# schematic.net
KiCad netlist of a schematic drawn in Altium Designer
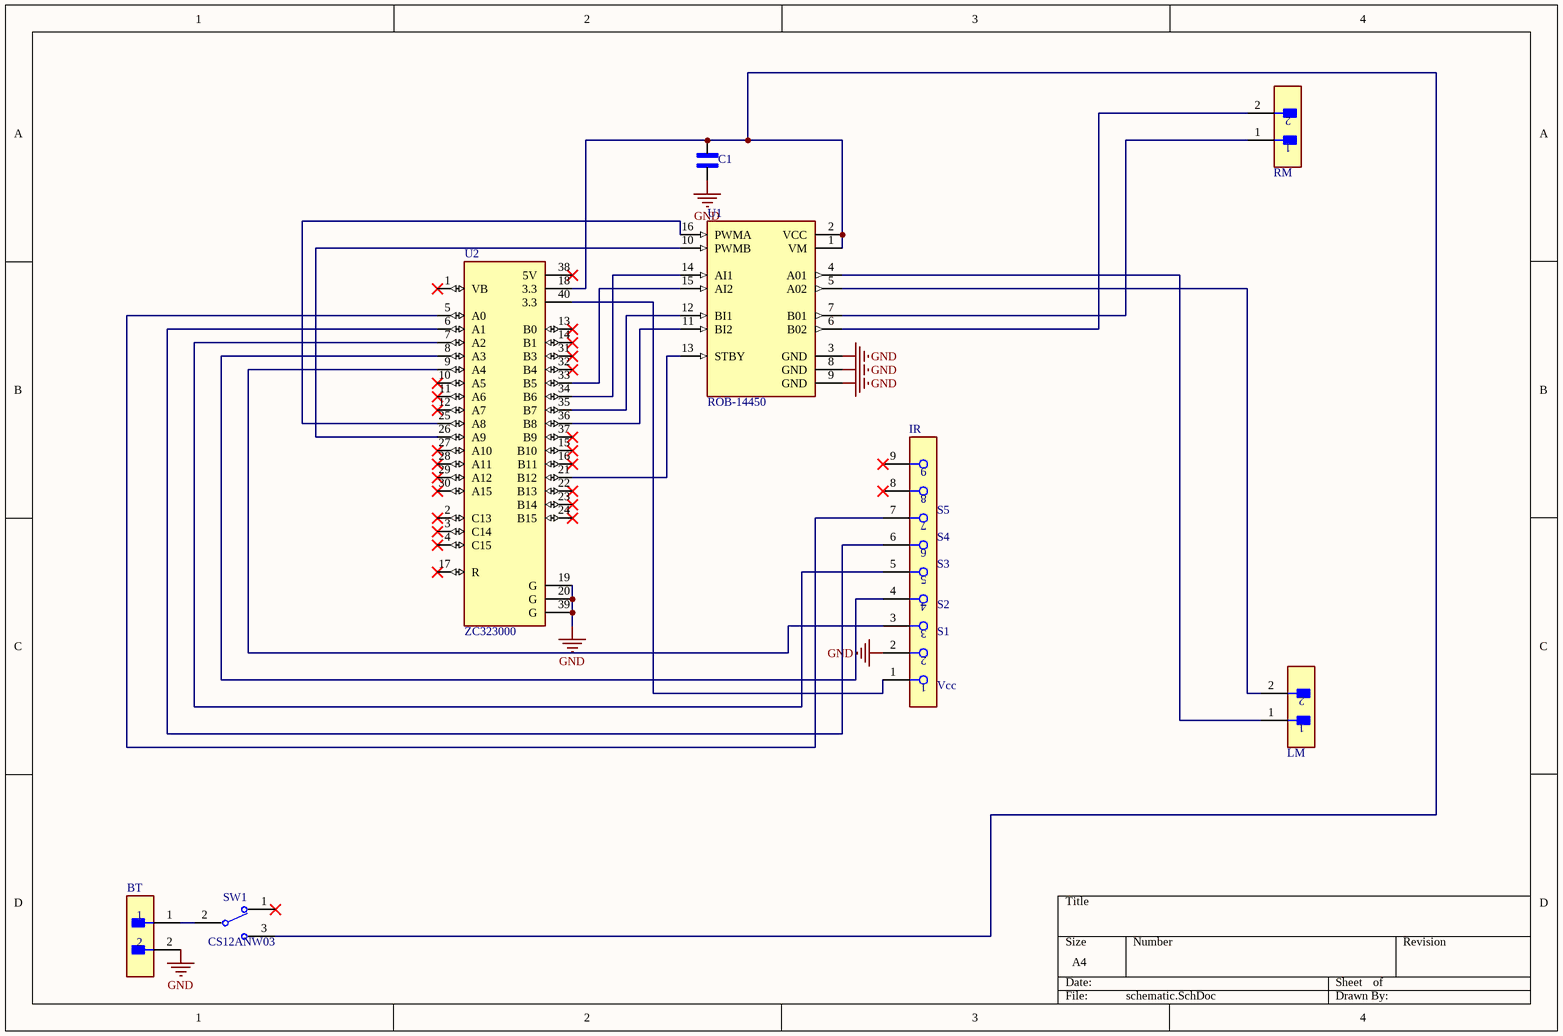
[diagram p0: schematic.SchDoc]

(export (version "E")
  (design (tool "Eeschema 10.0.6"))
  (components
    (comp (ref "BT")
      (value "B2B-XH-AM(LF)(SN)")
      (footprint "FP-B2B-XH-AM_LF_SN-MFG")
      (description "CONN HEADER VERT 2POS 2.5MM")
      (libsource (lib "") (part "3bc925449376181038e59eaffc5286c_1"))
    )
    (comp (ref "C1")
      (value "FA14X8R1H104KNU06")
      (footprint "CAPRB250W50L450T300H550")
      (description "0.1 ÂµF Â±10% 50V Ceramic Capacitor X8R Radial")
      (fields (field (name "MF") "TDK"))
      (libsource (lib "Capacitor_0.1uf") (part "FA14X8R1H104KNU06"))
    )
    (comp (ref "IR")
      (value "CES-109-01-G-S")
      (footprint "FP-CES-109-01-G-S-MFG")
      (description "CES-109-01-G-S Conn Socket Strip SKT 9 POS 2.54mm Solder ST Top Entry Thru-Hole Tube")
      (libsource (lib "Altium Content Vault") (part "d3bf64047269a9dc9b641cdda8ee9d2"))
    )
    (comp (ref "LM")
      (value "TSW-102-12-T-S")
      (footprint "FP-TSW-102-12-T-S-MFG")
      (description "CONN HEADER VERT 2POS 2.54MM")
      (libsource (lib "Altium Content Vault") (part "3bc925449376181038e59eaffc5286c"))
    )
    (comp (ref "RM")
      (value "TSW-102-12-T-S")
      (footprint "FP-TSW-102-12-T-S-MFG")
      (description "CONN HEADER VERT 2POS 2.54MM")
      (libsource (lib "Altium Content Vault") (part "3bc925449376181038e59eaffc5286c"))
    )
    (comp (ref "SW1")
      (value "CS12ANW03")
      (footprint "FP-CS12ANW03-MFG")
      (description "SWITCH SLIDE SPDT 3A 125V")
      (libsource (lib "Altium Content Vault") (part "12161840acc88c497b895bf2e19a5b1"))
    )
    (comp (ref "U1")
      (value "ROB-14450")
      (footprint "MODULE_ROB-14450")
      (description "TB6612FNG Motor Controller/Driver Power Management Evaluation Board")
      (fields (field (name "MF") "SparkFun Electronics"))
      (libsource (lib "DRIVER") (part "ROB-14450"))
    )
    (comp (ref "U2")
      (value "ZC323000")
      (footprint "MODULE_ZC323000")
      (description "STM32F103C8T6 ARM STM32 Minimum System Development Board Module For Arduino")
      (libsource (lib "STM32") (part "ZC323000"))
    )
  )
  (nets
    (net (code "1") (name "GND") (class "Default")
      (node (ref "BT") (pin "2") (pinfunction "2_2") (pintype "passive"))
      (node (ref "C1") (pin "1") (pinfunction "1_1") (pintype "passive"))
      (node (ref "IR") (pin "2") (pinfunction "2_2") (pintype "passive"))
      (node (ref "U1") (pin "3") (pinfunction "GND_3") (pintype "power_in"))
      (node (ref "U1") (pin "8") (pinfunction "GND_8") (pintype "power_in"))
      (node (ref "U1") (pin "9") (pinfunction "GND_9") (pintype "power_in"))
      (node (ref "U2") (pin "19") (pinfunction "G_19") (pintype "power_in"))
      (node (ref "U2") (pin "20") (pinfunction "G_20") (pintype "power_in"))
      (node (ref "U2") (pin "39") (pinfunction "G_39") (pintype "power_in"))
    )
    (net (code "2") (name "Net-(IR-Pad1)") (class "Default")
      (node (ref "IR") (pin "1") (pinfunction "1_1") (pintype "passive"))
      (node (ref "U2") (pin "40") (pinfunction "3.3_40") (pintype "power_in"))
    )
    (net (code "3") (name "Net-(SW1-2(COM))") (class "Default")
      (node (ref "BT") (pin "1") (pinfunction "1_1") (pintype "passive"))
      (node (ref "SW1") (pin "2") (pinfunction "2(COM)_2") (pintype "passive"))
    )
    (net (code "4") (name "Net-(U1-A01)") (class "Default")
      (node (ref "LM") (pin "1") (pinfunction "1_1") (pintype "passive"))
      (node (ref "U1") (pin "4") (pinfunction "A01_4") (pintype "output"))
    )
    (net (code "5") (name "Net-(U1-A02)") (class "Default")
      (node (ref "LM") (pin "2") (pinfunction "2_2") (pintype "passive"))
      (node (ref "U1") (pin "5") (pinfunction "A02_5") (pintype "output"))
    )
    (net (code "6") (name "Net-(U1-AI1)") (class "Default")
      (node (ref "U1") (pin "14") (pinfunction "AI1_14") (pintype "input"))
      (node (ref "U2") (pin "34") (pinfunction "B6_34") (pintype "bidirectional"))
    )
    (net (code "7") (name "Net-(U1-AI2)") (class "Default")
      (node (ref "U1") (pin "15") (pinfunction "AI2_15") (pintype "input"))
      (node (ref "U2") (pin "33") (pinfunction "B5_33") (pintype "bidirectional"))
    )
    (net (code "8") (name "Net-(U1-B01)") (class "Default")
      (node (ref "RM") (pin "1") (pinfunction "1_1") (pintype "passive"))
      (node (ref "U1") (pin "7") (pinfunction "B01_7") (pintype "output"))
    )
    (net (code "9") (name "Net-(U1-B02)") (class "Default")
      (node (ref "RM") (pin "2") (pinfunction "2_2") (pintype "passive"))
      (node (ref "U1") (pin "6") (pinfunction "B02_6") (pintype "output"))
    )
    (net (code "10") (name "Net-(U1-BI1)") (class "Default")
      (node (ref "U1") (pin "12") (pinfunction "BI1_12") (pintype "input"))
      (node (ref "U2") (pin "35") (pinfunction "B7_35") (pintype "bidirectional"))
    )
    (net (code "11") (name "Net-(U1-BI2)") (class "Default")
      (node (ref "U1") (pin "11") (pinfunction "BI2_11") (pintype "input"))
      (node (ref "U2") (pin "36") (pinfunction "B8_36") (pintype "bidirectional"))
    )
    (net (code "12") (name "Net-(U1-PWMA)") (class "Default")
      (node (ref "U1") (pin "16") (pinfunction "PWMA_16") (pintype "input"))
      (node (ref "U2") (pin "25") (pinfunction "A8_25") (pintype "bidirectional"))
    )
    (net (code "13") (name "Net-(U1-PWMB)") (class "Default")
      (node (ref "U1") (pin "10") (pinfunction "PWMB_10") (pintype "input"))
      (node (ref "U2") (pin "26") (pinfunction "A9_26") (pintype "bidirectional"))
    )
    (net (code "14") (name "Net-(U1-STBY)") (class "Default")
      (node (ref "U1") (pin "13") (pinfunction "STBY_13") (pintype "input"))
      (node (ref "U2") (pin "21") (pinfunction "B12_21") (pintype "bidirectional"))
    )
    (net (code "15") (name "Net-(U1-VCC)") (class "Default")
      (node (ref "C1") (pin "2") (pinfunction "2_2") (pintype "passive"))
      (node (ref "SW1") (pin "3") (pinfunction "3_3") (pintype "passive"))
      (node (ref "U1") (pin "1") (pinfunction "VM_1") (pintype "power_in"))
      (node (ref "U1") (pin "2") (pinfunction "VCC_2") (pintype "power_in"))
      (node (ref "U2") (pin "18") (pinfunction "3.3_18") (pintype "power_in"))
    )
    (net (code "16") (name "Net-(U2-A0)") (class "Default")
      (node (ref "IR") (pin "7") (pinfunction "7_7") (pintype "passive"))
      (node (ref "U2") (pin "5") (pinfunction "A0_5") (pintype "bidirectional"))
    )
    (net (code "17") (name "Net-(U2-A1)") (class "Default")
      (node (ref "IR") (pin "6") (pinfunction "6_6") (pintype "passive"))
      (node (ref "U2") (pin "6") (pinfunction "A1_6") (pintype "bidirectional"))
    )
    (net (code "18") (name "Net-(U2-A2)") (class "Default")
      (node (ref "IR") (pin "5") (pinfunction "5_5") (pintype "passive"))
      (node (ref "U2") (pin "7") (pinfunction "A2_7") (pintype "bidirectional"))
    )
    (net (code "19") (name "Net-(U2-A3)") (class "Default")
      (node (ref "IR") (pin "4") (pinfunction "4_4") (pintype "passive"))
      (node (ref "U2") (pin "8") (pinfunction "A3_8") (pintype "bidirectional"))
    )
    (net (code "20") (name "Net-(U2-A4)") (class "Default")
      (node (ref "IR") (pin "3") (pinfunction "3_3") (pintype "passive"))
      (node (ref "U2") (pin "9") (pinfunction "A4_9") (pintype "bidirectional"))
    )
    (net (code "21") (name "unconnected-(IR-Pad8)") (class "Default")
      (node (ref "IR") (pin "8") (pinfunction "8_8") (pintype "passive+no_connect"))
    )
    (net (code "22") (name "unconnected-(IR-Pad9)") (class "Default")
      (node (ref "IR") (pin "9") (pinfunction "9_9") (pintype "passive+no_connect"))
    )
    (net (code "23") (name "unconnected-(SW1-Pad1)") (class "Default")
      (node (ref "SW1") (pin "1") (pinfunction "1_1") (pintype "passive+no_connect"))
    )
    (net (code "24") (name "unconnected-(U2-5V-Pad38)") (class "Default")
      (node (ref "U2") (pin "38") (pinfunction "5V_38") (pintype "power_in+no_connect"))
    )
    (net (code "25") (name "unconnected-(U2-A5-Pad10)") (class "Default")
      (node (ref "U2") (pin "10") (pinfunction "A5_10") (pintype "bidirectional+no_connect"))
    )
    (net (code "26") (name "unconnected-(U2-A6-Pad11)") (class "Default")
      (node (ref "U2") (pin "11") (pinfunction "A6_11") (pintype "bidirectional+no_connect"))
    )
    (net (code "27") (name "unconnected-(U2-A7-Pad12)") (class "Default")
      (node (ref "U2") (pin "12") (pinfunction "A7_12") (pintype "bidirectional+no_connect"))
    )
    (net (code "28") (name "unconnected-(U2-A10-Pad27)") (class "Default")
      (node (ref "U2") (pin "27") (pinfunction "A10_27") (pintype "bidirectional+no_connect"))
    )
    (net (code "29") (name "unconnected-(U2-A11-Pad28)") (class "Default")
      (node (ref "U2") (pin "28") (pinfunction "A11_28") (pintype "bidirectional+no_connect"))
    )
    (net (code "30") (name "unconnected-(U2-A12-Pad29)") (class "Default")
      (node (ref "U2") (pin "29") (pinfunction "A12_29") (pintype "bidirectional+no_connect"))
    )
    (net (code "31") (name "unconnected-(U2-A15-Pad30)") (class "Default")
      (node (ref "U2") (pin "30") (pinfunction "A15_30") (pintype "bidirectional+no_connect"))
    )
    (net (code "32") (name "unconnected-(U2-B0-Pad13)") (class "Default")
      (node (ref "U2") (pin "13") (pinfunction "B0_13") (pintype "bidirectional+no_connect"))
    )
    (net (code "33") (name "unconnected-(U2-B1-Pad14)") (class "Default")
      (node (ref "U2") (pin "14") (pinfunction "B1_14") (pintype "bidirectional+no_connect"))
    )
    (net (code "34") (name "unconnected-(U2-B3-Pad31)") (class "Default")
      (node (ref "U2") (pin "31") (pinfunction "B3_31") (pintype "bidirectional+no_connect"))
    )
    (net (code "35") (name "unconnected-(U2-B4-Pad32)") (class "Default")
      (node (ref "U2") (pin "32") (pinfunction "B4_32") (pintype "bidirectional+no_connect"))
    )
    (net (code "36") (name "unconnected-(U2-B9-Pad37)") (class "Default")
      (node (ref "U2") (pin "37") (pinfunction "B9_37") (pintype "bidirectional+no_connect"))
    )
    (net (code "37") (name "unconnected-(U2-B10-Pad15)") (class "Default")
      (node (ref "U2") (pin "15") (pinfunction "B10_15") (pintype "bidirectional+no_connect"))
    )
    (net (code "38") (name "unconnected-(U2-B11-Pad16)") (class "Default")
      (node (ref "U2") (pin "16") (pinfunction "B11_16") (pintype "bidirectional+no_connect"))
    )
    (net (code "39") (name "unconnected-(U2-B13-Pad22)") (class "Default")
      (node (ref "U2") (pin "22") (pinfunction "B13_22") (pintype "bidirectional+no_connect"))
    )
    (net (code "40") (name "unconnected-(U2-B14-Pad23)") (class "Default")
      (node (ref "U2") (pin "23") (pinfunction "B14_23") (pintype "bidirectional+no_connect"))
    )
    (net (code "41") (name "unconnected-(U2-B15-Pad24)") (class "Default")
      (node (ref "U2") (pin "24") (pinfunction "B15_24") (pintype "bidirectional+no_connect"))
    )
    (net (code "42") (name "unconnected-(U2-C13-Pad2)") (class "Default")
      (node (ref "U2") (pin "2") (pinfunction "C13_2") (pintype "bidirectional+no_connect"))
    )
    (net (code "43") (name "unconnected-(U2-C14-Pad3)") (class "Default")
      (node (ref "U2") (pin "3") (pinfunction "C14_3") (pintype "bidirectional+no_connect"))
    )
    (net (code "44") (name "unconnected-(U2-C15-Pad4)") (class "Default")
      (node (ref "U2") (pin "4") (pinfunction "C15_4") (pintype "bidirectional+no_connect"))
    )
    (net (code "45") (name "unconnected-(U2-R-Pad17)") (class "Default")
      (node (ref "U2") (pin "17") (pinfunction "R_17") (pintype "bidirectional+no_connect"))
    )
    (net (code "46") (name "unconnected-(U2-VB-Pad1)") (class "Default")
      (node (ref "U2") (pin "1") (pinfunction "VB_1") (pintype "bidirectional+no_connect"))
    )
  )
)
